# scHnRk_3.net
KiCad netlist of a schematic drawn in EAGLE
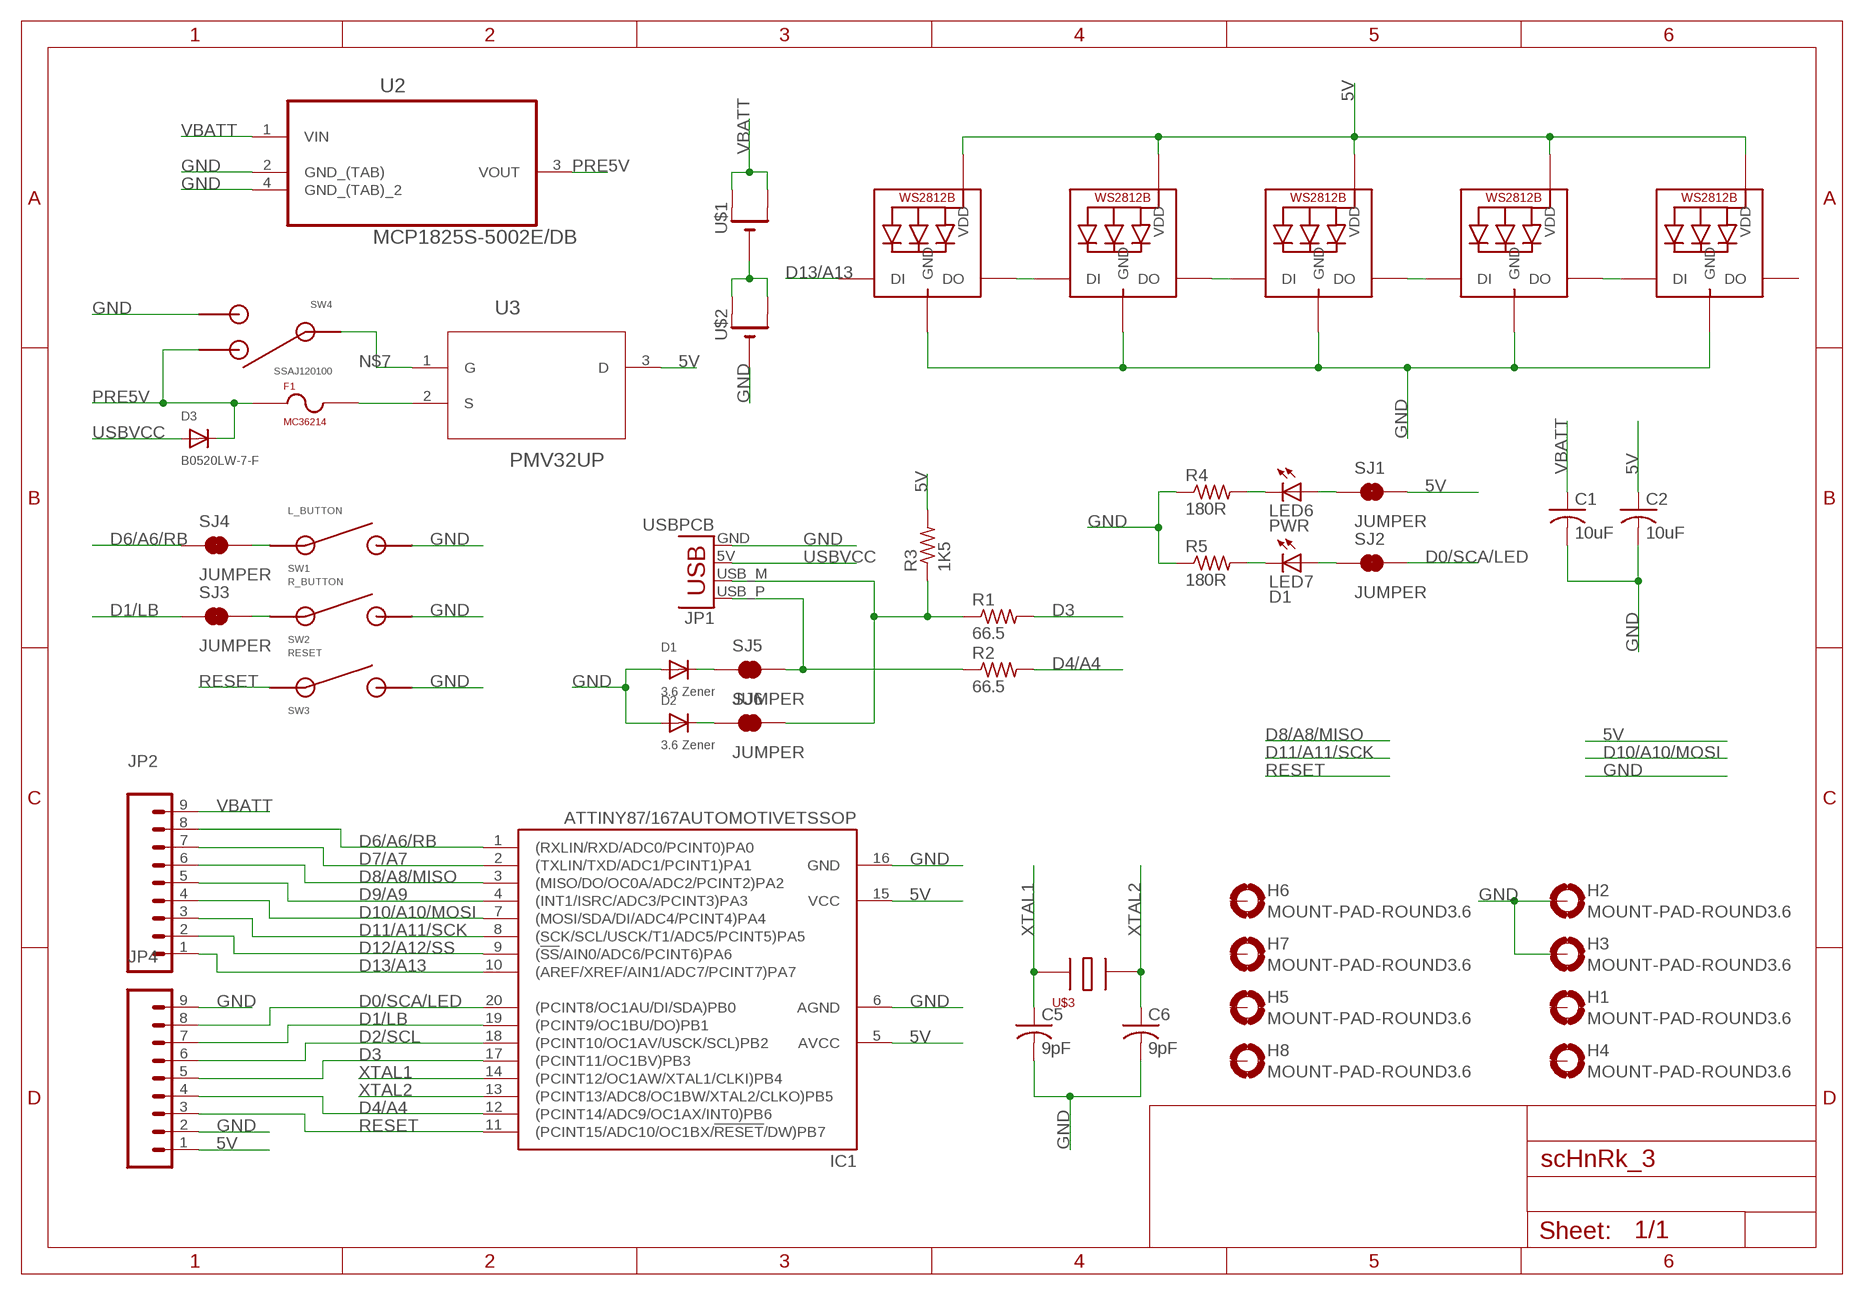
[diagram p0: schematic, sheet 1]

(export (version "E")
  (design (tool "Eeschema 10.0.6"))
  (components
    (comp (ref "C1")
      (value "10uF")
      (footprint "eagle-import:C1206K")
      (libsource (lib "eagle-import") (part "C-USC1206K"))
    )
    (comp (ref "C2")
      (value "10uF")
      (footprint "eagle-import:C1206K")
      (libsource (lib "eagle-import") (part "C-USC1206K"))
    )
    (comp (ref "C5")
      (value "9pF")
      (footprint "eagle-import:C0603K")
      (libsource (lib "eagle-import") (part "C-USC0603K"))
    )
    (comp (ref "C6")
      (value "9pF")
      (footprint "eagle-import:C0603K")
      (libsource (lib "eagle-import") (part "C-USC0603K"))
    )
    (comp (ref "D1")
      (value "3.6 Zener")
      (footprint "eagle-import:SOD-523")
      (libsource (lib "eagle-import") (part "DIODESOD-523"))
    )
    (comp (ref "D2")
      (value "3.6 Zener")
      (footprint "eagle-import:SOD-523")
      (libsource (lib "eagle-import") (part "DIODESOD-523"))
    )
    (comp (ref "D3")
      (value "B0520LW-7-F")
      (footprint "eagle-import:SOD-123")
      (libsource (lib "eagle-import") (part "DIODESOD-123"))
    )
    (comp (ref "F1")
      (value "MC36214")
      (footprint "eagle-import:MC36214")
      (libsource (lib "eagle-import") (part "MC36214"))
    )
    (comp (ref "H1")
      (value "MOUNT-PAD-ROUND3.6")
      (footprint "eagle-import:3,6-PAD")
      (libsource (lib "eagle-import") (part "MOUNT-PAD-ROUND3.6"))
    )
    (comp (ref "H2")
      (value "MOUNT-PAD-ROUND3.6")
      (footprint "eagle-import:3,6-PAD")
      (libsource (lib "eagle-import") (part "MOUNT-PAD-ROUND3.6"))
    )
    (comp (ref "H3")
      (value "MOUNT-PAD-ROUND3.6")
      (footprint "eagle-import:3,6-PAD")
      (libsource (lib "eagle-import") (part "MOUNT-PAD-ROUND3.6"))
    )
    (comp (ref "H4")
      (value "MOUNT-PAD-ROUND3.6")
      (footprint "eagle-import:3,6-PAD")
      (libsource (lib "eagle-import") (part "MOUNT-PAD-ROUND3.6"))
    )
    (comp (ref "H5")
      (value "MOUNT-PAD-ROUND3.6")
      (footprint "eagle-import:3,6-PAD")
      (libsource (lib "eagle-import") (part "MOUNT-PAD-ROUND3.6"))
    )
    (comp (ref "H6")
      (value "MOUNT-PAD-ROUND3.6")
      (footprint "eagle-import:3,6-PAD")
      (libsource (lib "eagle-import") (part "MOUNT-PAD-ROUND3.6"))
    )
    (comp (ref "H7")
      (value "MOUNT-PAD-ROUND3.6")
      (footprint "eagle-import:3,6-PAD")
      (libsource (lib "eagle-import") (part "MOUNT-PAD-ROUND3.6"))
    )
    (comp (ref "H8")
      (value "MOUNT-PAD-ROUND3.6")
      (footprint "eagle-import:3,6-PAD")
      (libsource (lib "eagle-import") (part "MOUNT-PAD-ROUND3.6"))
    )
    (comp (ref "IC1")
      (value "ATTINY87/167AUTOMOTIVETSSOP")
      (footprint "eagle-import:TSSOP20")
      (libsource (lib "eagle-import") (part "ATTINY87/167AUTOMOTIVETSSOP"))
    )
    (comp (ref "JP1")
      (value "USBPCB")
      (footprint "eagle-import:USB-A-PCB")
      (libsource (lib "eagle-import") (part "USBPCB"))
    )
    (comp (ref "JP2")
      (value "M09")
      (footprint "eagle-import:1X09")
      (libsource (lib "eagle-import") (part "M09"))
    )
    (comp (ref "JP4")
      (value "M09")
      (footprint "eagle-import:1X09")
      (libsource (lib "eagle-import") (part "M09"))
    )
    (comp (ref "LED1")
      (value "WS2812B5050")
      (footprint "eagle-import:WS2812B")
      (libsource (lib "eagle-import") (part "WS2812B5050"))
    )
    (comp (ref "LED2")
      (value "WS2812B5050")
      (footprint "eagle-import:WS2812B")
      (libsource (lib "eagle-import") (part "WS2812B5050"))
    )
    (comp (ref "LED3")
      (value "WS2812B5050")
      (footprint "eagle-import:WS2812B")
      (libsource (lib "eagle-import") (part "WS2812B5050"))
    )
    (comp (ref "LED4")
      (value "WS2812B5050")
      (footprint "eagle-import:WS2812B")
      (libsource (lib "eagle-import") (part "WS2812B5050"))
    )
    (comp (ref "LED5")
      (value "WS2812B5050")
      (footprint "eagle-import:WS2812B")
      (libsource (lib "eagle-import") (part "WS2812B5050"))
    )
    (comp (ref "LED6")
      (value "PWR")
      (footprint "eagle-import:CHIPLED_0603")
      (libsource (lib "eagle-import") (part "LEDCHIPLED_0603"))
    )
    (comp (ref "LED7")
      (value "D1")
      (footprint "eagle-import:CHIPLED_0603")
      (libsource (lib "eagle-import") (part "LEDCHIPLED_0603"))
    )
    (comp (ref "R1")
      (value "66.5")
      (footprint "eagle-import:R0603")
      (libsource (lib "eagle-import") (part "R-US_R0603"))
    )
    (comp (ref "R2")
      (value "66.5")
      (footprint "eagle-import:R0603")
      (libsource (lib "eagle-import") (part "R-US_R0603"))
    )
    (comp (ref "R3")
      (value "1K5")
      (footprint "eagle-import:R0603")
      (libsource (lib "eagle-import") (part "R-US_R0603"))
    )
    (comp (ref "R4")
      (value "180R")
      (footprint "eagle-import:R0603")
      (libsource (lib "eagle-import") (part "R-US_R0603"))
    )
    (comp (ref "R5")
      (value "180R")
      (footprint "eagle-import:R0603")
      (libsource (lib "eagle-import") (part "R-US_R0603"))
    )
    (comp (ref "SJ1")
      (value "JUMPER")
      (footprint "eagle-import:PAD-JUMPER-2-NC_BY_TRACE_YES_SILK")
      (libsource (lib "eagle-import") (part "JUMPER-PAD-2-NC_BY_TRACE"))
    )
    (comp (ref "SJ2")
      (value "JUMPER")
      (footprint "eagle-import:PAD-JUMPER-2-NC_BY_TRACE_YES_SILK")
      (libsource (lib "eagle-import") (part "JUMPER-PAD-2-NC_BY_TRACE"))
    )
    (comp (ref "SJ3")
      (value "JUMPER")
      (footprint "eagle-import:PAD-JUMPER-2-NC_BY_TRACE_YES_SILK")
      (libsource (lib "eagle-import") (part "JUMPER-PAD-2-NC_BY_TRACE"))
    )
    (comp (ref "SJ4")
      (value "JUMPER")
      (footprint "eagle-import:PAD-JUMPER-2-NC_BY_TRACE_YES_SILK")
      (libsource (lib "eagle-import") (part "JUMPER-PAD-2-NC_BY_TRACE"))
    )
    (comp (ref "SJ5")
      (value "JUMPER")
      (footprint "eagle-import:PAD-JUMPER-2-NC_BY_TRACE_YES_SILK")
      (libsource (lib "eagle-import") (part "JUMPER-PAD-2-NC_BY_TRACE"))
    )
    (comp (ref "SJ6")
      (value "JUMPER")
      (footprint "eagle-import:PAD-JUMPER-2-NC_BY_TRACE_YES_SILK")
      (libsource (lib "eagle-import") (part "JUMPER-PAD-2-NC_BY_TRACE"))
    )
    (comp (ref "SW1")
      (value "L_BUTTON")
      (footprint "eagle-import:SKRBAGE010")
      (libsource (lib "eagle-import") (part "SKRBAGE010"))
    )
    (comp (ref "SW2")
      (value "R_BUTTON")
      (footprint "eagle-import:SKRBAGE010")
      (libsource (lib "eagle-import") (part "SKRBAGE010"))
    )
    (comp (ref "SW3")
      (value "RESET")
      (footprint "eagle-import:SKRBAGE010")
      (libsource (lib "eagle-import") (part "SKRBAGE010"))
    )
    (comp (ref "SW4")
      (value "SSAJ120100")
      (footprint "eagle-import:SSAJ120100")
      (libsource (lib "eagle-import") (part "SSAJ120100"))
    )
    (comp (ref "U$1")
      (value "CR2032SMT")
      (footprint "eagle-import:CR2032-SMD")
      (libsource (lib "eagle-import") (part "CR2032SMT"))
    )
    (comp (ref "U$2")
      (value "CR2032SMT")
      (footprint "eagle-import:CR2032-SMD")
      (libsource (lib "eagle-import") (part "CR2032SMT"))
    )
    (comp (ref "U$3")
      (value "16MHZ-2467444")
      (footprint "eagle-import:16MHZ-2467444")
      (libsource (lib "eagle-import") (part "16MHZ-2467444"))
    )
    (comp (ref "U2")
      (value "MCP1825S-5002E/DB")
      (footprint "eagle-import:SOT230P700X180-4N")
      (libsource (lib "eagle-import") (part "MCP1825S-5002E/DB"))
    )
    (comp (ref "U3")
      (value "PMV32UP")
      (footprint "eagle-import:SOT95P230X110-3N")
      (libsource (lib "eagle-import") (part "PMV32UP"))
    )
  )
  (nets
    (net (code "1") (name "/5V") (class "Default")
      (node (ref "C2") (pin "1") (pinfunction "1_1") (pintype "passive"))
      (node (ref "IC1") (pin "15") (pinfunction "VCC_15") (pintype "power_in"))
      (node (ref "IC1") (pin "5") (pinfunction "AVCC_5") (pintype "bidirectional"))
      (node (ref "JP4") (pin "1") (pinfunction "1_1") (pintype "passive"))
      (node (ref "LED1") (pin "1-VDD") (pinfunction "VDD_1-VDD") (pintype "power_in"))
      (node (ref "LED2") (pin "1-VDD") (pinfunction "VDD_1-VDD") (pintype "power_in"))
      (node (ref "LED3") (pin "1-VDD") (pinfunction "VDD_1-VDD") (pintype "power_in"))
      (node (ref "LED4") (pin "1-VDD") (pinfunction "VDD_1-VDD") (pintype "power_in"))
      (node (ref "LED5") (pin "1-VDD") (pinfunction "VDD_1-VDD") (pintype "power_in"))
      (node (ref "R3") (pin "2") (pinfunction "2_2") (pintype "passive"))
      (node (ref "SJ1") (pin "2") (pinfunction "2_2") (pintype "passive"))
      (node (ref "U3") (pin "3") (pinfunction "D_3") (pintype "passive"))
    )
    (net (code "2") (name "/D0{slash}SCA{slash}LED") (class "Default")
      (node (ref "IC1") (pin "20") (pinfunction "(PCINT8/OC1AU/DI/SDA)PB0_20") (pintype "bidirectional"))
      (node (ref "JP4") (pin "8") (pinfunction "8_8") (pintype "passive"))
      (node (ref "SJ2") (pin "2") (pinfunction "2_2") (pintype "passive"))
    )
    (net (code "3") (name "/D1{slash}LB") (class "Default")
      (node (ref "IC1") (pin "19") (pinfunction "(PCINT9/OC1BU/DO)PB1_19") (pintype "bidirectional"))
      (node (ref "JP4") (pin "7") (pinfunction "7_7") (pintype "passive"))
      (node (ref "SJ3") (pin "1") (pinfunction "1_1") (pintype "passive"))
    )
    (net (code "4") (name "/D2{slash}SCL") (class "Default")
      (node (ref "IC1") (pin "18") (pinfunction "(PCINT10/OC1AV/USCK/SCL)PB2_18") (pintype "bidirectional"))
      (node (ref "JP4") (pin "6") (pinfunction "6_6") (pintype "passive"))
    )
    (net (code "5") (name "/D3") (class "Default")
      (node (ref "IC1") (pin "17") (pinfunction "(PCINT11/OC1BV)PB3_17") (pintype "bidirectional"))
      (node (ref "JP4") (pin "5") (pinfunction "5_5") (pintype "passive"))
      (node (ref "R1") (pin "2") (pinfunction "2_2") (pintype "passive"))
    )
    (net (code "6") (name "/D4{slash}A4") (class "Default")
      (node (ref "IC1") (pin "12") (pinfunction "(PCINT14/ADC9/OC1AX/INT0)PB6_12") (pintype "bidirectional"))
      (node (ref "JP4") (pin "4") (pinfunction "4_4") (pintype "passive"))
      (node (ref "R2") (pin "2") (pinfunction "2_2") (pintype "passive"))
    )
    (net (code "7") (name "/D6{slash}A6{slash}RB") (class "Default")
      (node (ref "IC1") (pin "1") (pinfunction "(RXLIN/RXD/ADC0/PCINT0)PA0_1") (pintype "bidirectional"))
      (node (ref "JP2") (pin "8") (pinfunction "8_8") (pintype "passive"))
      (node (ref "SJ4") (pin "1") (pinfunction "1_1") (pintype "passive"))
    )
    (net (code "8") (name "/D7{slash}A7") (class "Default")
      (node (ref "IC1") (pin "2") (pinfunction "(TXLIN/TXD/ADC1/PCINT1)PA1_2") (pintype "bidirectional"))
      (node (ref "JP2") (pin "7") (pinfunction "7_7") (pintype "passive"))
    )
    (net (code "9") (name "/D8{slash}A8{slash}MISO") (class "Default")
      (node (ref "IC1") (pin "3") (pinfunction "(MISO/DO/OC0A/ADC2/PCINT2)PA2_3") (pintype "bidirectional"))
      (node (ref "JP2") (pin "6") (pinfunction "6_6") (pintype "passive"))
    )
    (net (code "10") (name "/D9{slash}A9") (class "Default")
      (node (ref "IC1") (pin "4") (pinfunction "(INT1/ISRC/ADC3/PCINT3)PA3_4") (pintype "bidirectional"))
      (node (ref "JP2") (pin "5") (pinfunction "5_5") (pintype "passive"))
    )
    (net (code "11") (name "/D10{slash}A10{slash}MOSI") (class "Default")
      (node (ref "IC1") (pin "7") (pinfunction "(MOSI/SDA/DI/ADC4/PCINT4)PA4_7") (pintype "bidirectional"))
      (node (ref "JP2") (pin "4") (pinfunction "4_4") (pintype "passive"))
    )
    (net (code "12") (name "/D11{slash}A11{slash}SCK") (class "Default")
      (node (ref "IC1") (pin "8") (pinfunction "(SCK/SCL/USCK/T1/ADC5/PCINT5)PA5_8") (pintype "bidirectional"))
      (node (ref "JP2") (pin "3") (pinfunction "3_3") (pintype "passive"))
    )
    (net (code "13") (name "/D12{slash}A12{slash}SS") (class "Default")
      (node (ref "IC1") (pin "9") (pinfunction "(~{SS}/AIN0/ADC6/PCINT6)PA6_9") (pintype "bidirectional"))
      (node (ref "JP2") (pin "2") (pinfunction "2_2") (pintype "passive"))
    )
    (net (code "14") (name "/D13{slash}A13") (class "Default")
      (node (ref "IC1") (pin "10") (pinfunction "(AREF/XREF/AIN1/ADC7/PCINT7)PA7_10") (pintype "bidirectional"))
      (node (ref "JP2") (pin "1") (pinfunction "1_1") (pintype "passive"))
      (node (ref "LED1") (pin "4-DIN") (pinfunction "DI_4-DIN") (pintype "input"))
    )
    (net (code "15") (name "/GND") (class "Default")
      (node (ref "C1") (pin "2") (pinfunction "2_2") (pintype "passive"))
      (node (ref "C2") (pin "2") (pinfunction "2_2") (pintype "passive"))
      (node (ref "C5") (pin "2") (pinfunction "2_2") (pintype "passive"))
      (node (ref "C6") (pin "2") (pinfunction "2_2") (pintype "passive"))
      (node (ref "D1") (pin "A") (pinfunction "A_A") (pintype "passive"))
      (node (ref "D2") (pin "A") (pinfunction "A_A") (pintype "passive"))
      (node (ref "H2") (pin "B3,6") (pinfunction "MOUNT_B3,6") (pintype "passive"))
      (node (ref "H3") (pin "B3,6") (pinfunction "MOUNT_B3,6") (pintype "passive"))
      (node (ref "IC1") (pin "16") (pinfunction "GND_16") (pintype "power_in"))
      (node (ref "IC1") (pin "6") (pinfunction "AGND_6") (pintype "bidirectional"))
      (node (ref "JP1") (pin "GND") (pinfunction "GND_GND") (pintype "bidirectional"))
      (node (ref "JP4") (pin "2") (pinfunction "2_2") (pintype "passive"))
      (node (ref "JP4") (pin "9") (pinfunction "9_9") (pintype "passive"))
      (node (ref "LED1") (pin "3-GND") (pinfunction "GND_3-GND") (pintype "power_in"))
      (node (ref "LED2") (pin "3-GND") (pinfunction "GND_3-GND") (pintype "power_in"))
      (node (ref "LED3") (pin "3-GND") (pinfunction "GND_3-GND") (pintype "power_in"))
      (node (ref "LED4") (pin "3-GND") (pinfunction "GND_3-GND") (pintype "power_in"))
      (node (ref "LED5") (pin "3-GND") (pinfunction "GND_3-GND") (pintype "power_in"))
      (node (ref "R4") (pin "1") (pinfunction "1_1") (pintype "passive"))
      (node (ref "R5") (pin "1") (pinfunction "1_1") (pintype "passive"))
      (node (ref "SW1") (pin "P$2") (pinfunction "P$2_P$2") (pintype "bidirectional"))
      (node (ref "SW1") (pin "P$4") (pinfunction "P$2_P$4") (pintype "bidirectional"))
      (node (ref "SW2") (pin "P$2") (pinfunction "P$2_P$2") (pintype "bidirectional"))
      (node (ref "SW2") (pin "P$4") (pinfunction "P$2_P$4") (pintype "bidirectional"))
      (node (ref "SW3") (pin "P$2") (pinfunction "P$2_P$2") (pintype "bidirectional"))
      (node (ref "SW3") (pin "P$4") (pinfunction "P$2_P$4") (pintype "bidirectional"))
      (node (ref "SW4") (pin "P$2") (pinfunction "P$2_P$2") (pintype "bidirectional"))
      (node (ref "U$2") (pin "-") (pinfunction "-_-") (pintype "passive"))
      (node (ref "U2") (pin "2") (pinfunction "GND_(TAB)_2") (pintype "passive"))
      (node (ref "U2") (pin "4") (pinfunction "GND_(TAB)_2_4") (pintype "passive"))
    )
    (net (code "16") (name "/N$7") (class "Default")
      (node (ref "SW4") (pin "P$C") (pinfunction "P$C_P$C") (pintype "bidirectional"))
      (node (ref "U3") (pin "1") (pinfunction "G_1") (pintype "passive"))
    )
    (net (code "17") (name "/PRE5V") (class "Default")
      (node (ref "D3") (pin "C") (pinfunction "C_C") (pintype "passive"))
      (node (ref "F1") (pin "P$1") (pinfunction "P$1_P$1") (pintype "bidirectional"))
      (node (ref "SW4") (pin "P$1") (pinfunction "P$1_P$1") (pintype "bidirectional"))
      (node (ref "U2") (pin "3") (pinfunction "VOUT_3") (pintype "output"))
    )
    (net (code "18") (name "/RESET") (class "Default")
      (node (ref "IC1") (pin "11") (pinfunction "(PCINT15/ADC10/OC1BX/~{RESET}/DW)PB7_11") (pintype "bidirectional"))
      (node (ref "JP4") (pin "3") (pinfunction "3_3") (pintype "passive"))
      (node (ref "SW3") (pin "P$1") (pinfunction "P$1_P$1") (pintype "bidirectional"))
      (node (ref "SW3") (pin "P$3") (pinfunction "P$1_P$3") (pintype "bidirectional"))
    )
    (net (code "19") (name "/USBVCC") (class "Default")
      (node (ref "D3") (pin "A") (pinfunction "A_A") (pintype "passive"))
      (node (ref "JP1") (pin "5V") (pinfunction "VBUS_5V") (pintype "bidirectional"))
    )
    (net (code "20") (name "/VBATT") (class "Default")
      (node (ref "C1") (pin "1") (pinfunction "1_1") (pintype "passive"))
      (node (ref "JP2") (pin "9") (pinfunction "9_9") (pintype "passive"))
      (node (ref "U$1") (pin "+$1") (pinfunction "+_+$1") (pintype "passive"))
      (node (ref "U$1") (pin "+$2") (pinfunction "+1_+$2") (pintype "passive"))
      (node (ref "U2") (pin "1") (pinfunction "VIN_1") (pintype "input"))
    )
    (net (code "21") (name "/XTAL1") (class "Default")
      (node (ref "C5") (pin "1") (pinfunction "1_1") (pintype "passive"))
      (node (ref "IC1") (pin "14") (pinfunction "(PCINT12/OC1AW/XTAL1/CLKI)PB4_14") (pintype "bidirectional"))
      (node (ref "U$3") (pin "P$1") (pinfunction "P$1_P$1") (pintype "bidirectional"))
    )
    (net (code "22") (name "/XTAL2") (class "Default")
      (node (ref "C6") (pin "1") (pinfunction "1_1") (pintype "passive"))
      (node (ref "IC1") (pin "13") (pinfunction "(PCINT13/ADC8/OC1BW/XTAL2/CLKO)PB5_13") (pintype "bidirectional"))
      (node (ref "U$3") (pin "P$3") (pinfunction "P$2_P$3") (pintype "bidirectional"))
    )
    (net (code "23") (name "Net-(D1-C)") (class "Default")
      (node (ref "D1") (pin "K") (pinfunction "C_K") (pintype "passive"))
      (node (ref "SJ5") (pin "1") (pinfunction "1_1") (pintype "passive"))
    )
    (net (code "24") (name "Net-(D2-C)") (class "Default")
      (node (ref "D2") (pin "K") (pinfunction "C_K") (pintype "passive"))
      (node (ref "SJ6") (pin "1") (pinfunction "1_1") (pintype "passive"))
    )
    (net (code "25") (name "Net-(JP1-D+)") (class "Default")
      (node (ref "JP1") (pin "USB_P") (pinfunction "D+_USB_P") (pintype "bidirectional"))
      (node (ref "R2") (pin "1") (pinfunction "1_1") (pintype "passive"))
      (node (ref "SJ5") (pin "2") (pinfunction "2_2") (pintype "passive"))
    )
    (net (code "26") (name "Net-(JP1-D-)") (class "Default")
      (node (ref "JP1") (pin "USB_M") (pinfunction "D-_USB_M") (pintype "bidirectional"))
      (node (ref "R1") (pin "1") (pinfunction "1_1") (pintype "passive"))
      (node (ref "R3") (pin "1") (pinfunction "1_1") (pintype "passive"))
      (node (ref "SJ6") (pin "2") (pinfunction "2_2") (pintype "passive"))
    )
    (net (code "27") (name "Net-(LED1-DO)") (class "Default")
      (node (ref "LED1") (pin "2-DOUT") (pinfunction "DO_2-DOUT") (pintype "output"))
      (node (ref "LED2") (pin "4-DIN") (pinfunction "DI_4-DIN") (pintype "input"))
    )
    (net (code "28") (name "Net-(LED2-DO)") (class "Default")
      (node (ref "LED2") (pin "2-DOUT") (pinfunction "DO_2-DOUT") (pintype "output"))
      (node (ref "LED3") (pin "4-DIN") (pinfunction "DI_4-DIN") (pintype "input"))
    )
    (net (code "29") (name "Net-(LED3-DO)") (class "Default")
      (node (ref "LED3") (pin "2-DOUT") (pinfunction "DO_2-DOUT") (pintype "output"))
      (node (ref "LED4") (pin "4-DIN") (pinfunction "DI_4-DIN") (pintype "input"))
    )
    (net (code "30") (name "Net-(LED4-DO)") (class "Default")
      (node (ref "LED4") (pin "2-DOUT") (pinfunction "DO_2-DOUT") (pintype "output"))
      (node (ref "LED5") (pin "4-DIN") (pinfunction "DI_4-DIN") (pintype "input"))
    )
    (net (code "31") (name "Net-(LED6-PadA)") (class "Default")
      (node (ref "LED6") (pin "A") (pinfunction "A_A") (pintype "passive"))
      (node (ref "SJ1") (pin "1") (pinfunction "1_1") (pintype "passive"))
    )
    (net (code "32") (name "Net-(LED6-PadC)") (class "Default")
      (node (ref "LED6") (pin "C") (pinfunction "C_C") (pintype "passive"))
      (node (ref "R4") (pin "2") (pinfunction "2_2") (pintype "passive"))
    )
    (net (code "33") (name "Net-(LED7-PadA)") (class "Default")
      (node (ref "LED7") (pin "A") (pinfunction "A_A") (pintype "passive"))
      (node (ref "SJ2") (pin "1") (pinfunction "1_1") (pintype "passive"))
    )
    (net (code "34") (name "Net-(LED7-PadC)") (class "Default")
      (node (ref "LED7") (pin "C") (pinfunction "C_C") (pintype "passive"))
      (node (ref "R5") (pin "2") (pinfunction "2_2") (pintype "passive"))
    )
    (net (code "35") (name "Net-(SJ3-Pad2)") (class "Default")
      (node (ref "SJ3") (pin "2") (pinfunction "2_2") (pintype "passive"))
      (node (ref "SW2") (pin "P$1") (pinfunction "P$1_P$1") (pintype "bidirectional"))
      (node (ref "SW2") (pin "P$3") (pinfunction "P$1_P$3") (pintype "bidirectional"))
    )
    (net (code "36") (name "Net-(SJ4-Pad2)") (class "Default")
      (node (ref "SJ4") (pin "2") (pinfunction "2_2") (pintype "passive"))
      (node (ref "SW1") (pin "P$1") (pinfunction "P$1_P$1") (pintype "bidirectional"))
      (node (ref "SW1") (pin "P$3") (pinfunction "P$1_P$3") (pintype "bidirectional"))
    )
    (net (code "37") (name "Net-(U$2-+)") (class "Default")
      (node (ref "U$1") (pin "-") (pinfunction "-_-") (pintype "passive"))
      (node (ref "U$2") (pin "+$1") (pinfunction "+_+$1") (pintype "passive"))
      (node (ref "U$2") (pin "+$2") (pinfunction "+1_+$2") (pintype "passive"))
    )
    (net (code "38") (name "Net-(U3-S)") (class "Default")
      (node (ref "F1") (pin "P$2") (pinfunction "P$2_P$2") (pintype "bidirectional"))
      (node (ref "U3") (pin "2") (pinfunction "S_2") (pintype "passive"))
    )
    (net (code "39") (name "unconnected-(H1-MOUNT-PadB3,6)") (class "Default")
      (node (ref "H1") (pin "B3,6") (pinfunction "MOUNT_B3,6") (pintype "passive"))
    )
    (net (code "40") (name "unconnected-(H4-MOUNT-PadB3,6)") (class "Default")
      (node (ref "H4") (pin "B3,6") (pinfunction "MOUNT_B3,6") (pintype "passive"))
    )
    (net (code "41") (name "unconnected-(H5-MOUNT-PadB3,6)") (class "Default")
      (node (ref "H5") (pin "B3,6") (pinfunction "MOUNT_B3,6") (pintype "passive"))
    )
    (net (code "42") (name "unconnected-(H6-MOUNT-PadB3,6)") (class "Default")
      (node (ref "H6") (pin "B3,6") (pinfunction "MOUNT_B3,6") (pintype "passive"))
    )
    (net (code "43") (name "unconnected-(H7-MOUNT-PadB3,6)") (class "Default")
      (node (ref "H7") (pin "B3,6") (pinfunction "MOUNT_B3,6") (pintype "passive"))
    )
    (net (code "44") (name "unconnected-(H8-MOUNT-PadB3,6)") (class "Default")
      (node (ref "H8") (pin "B3,6") (pinfunction "MOUNT_B3,6") (pintype "passive"))
    )
    (net (code "45") (name "unconnected-(LED5-DO-Pad2-DOUT)") (class "Default")
      (node (ref "LED5") (pin "2-DOUT") (pinfunction "DO_2-DOUT") (pintype "output"))
    )
  )
)
